# Multi_Room_Fire_Detection.net
KiCad netlist of a schematic drawn in EAGLE
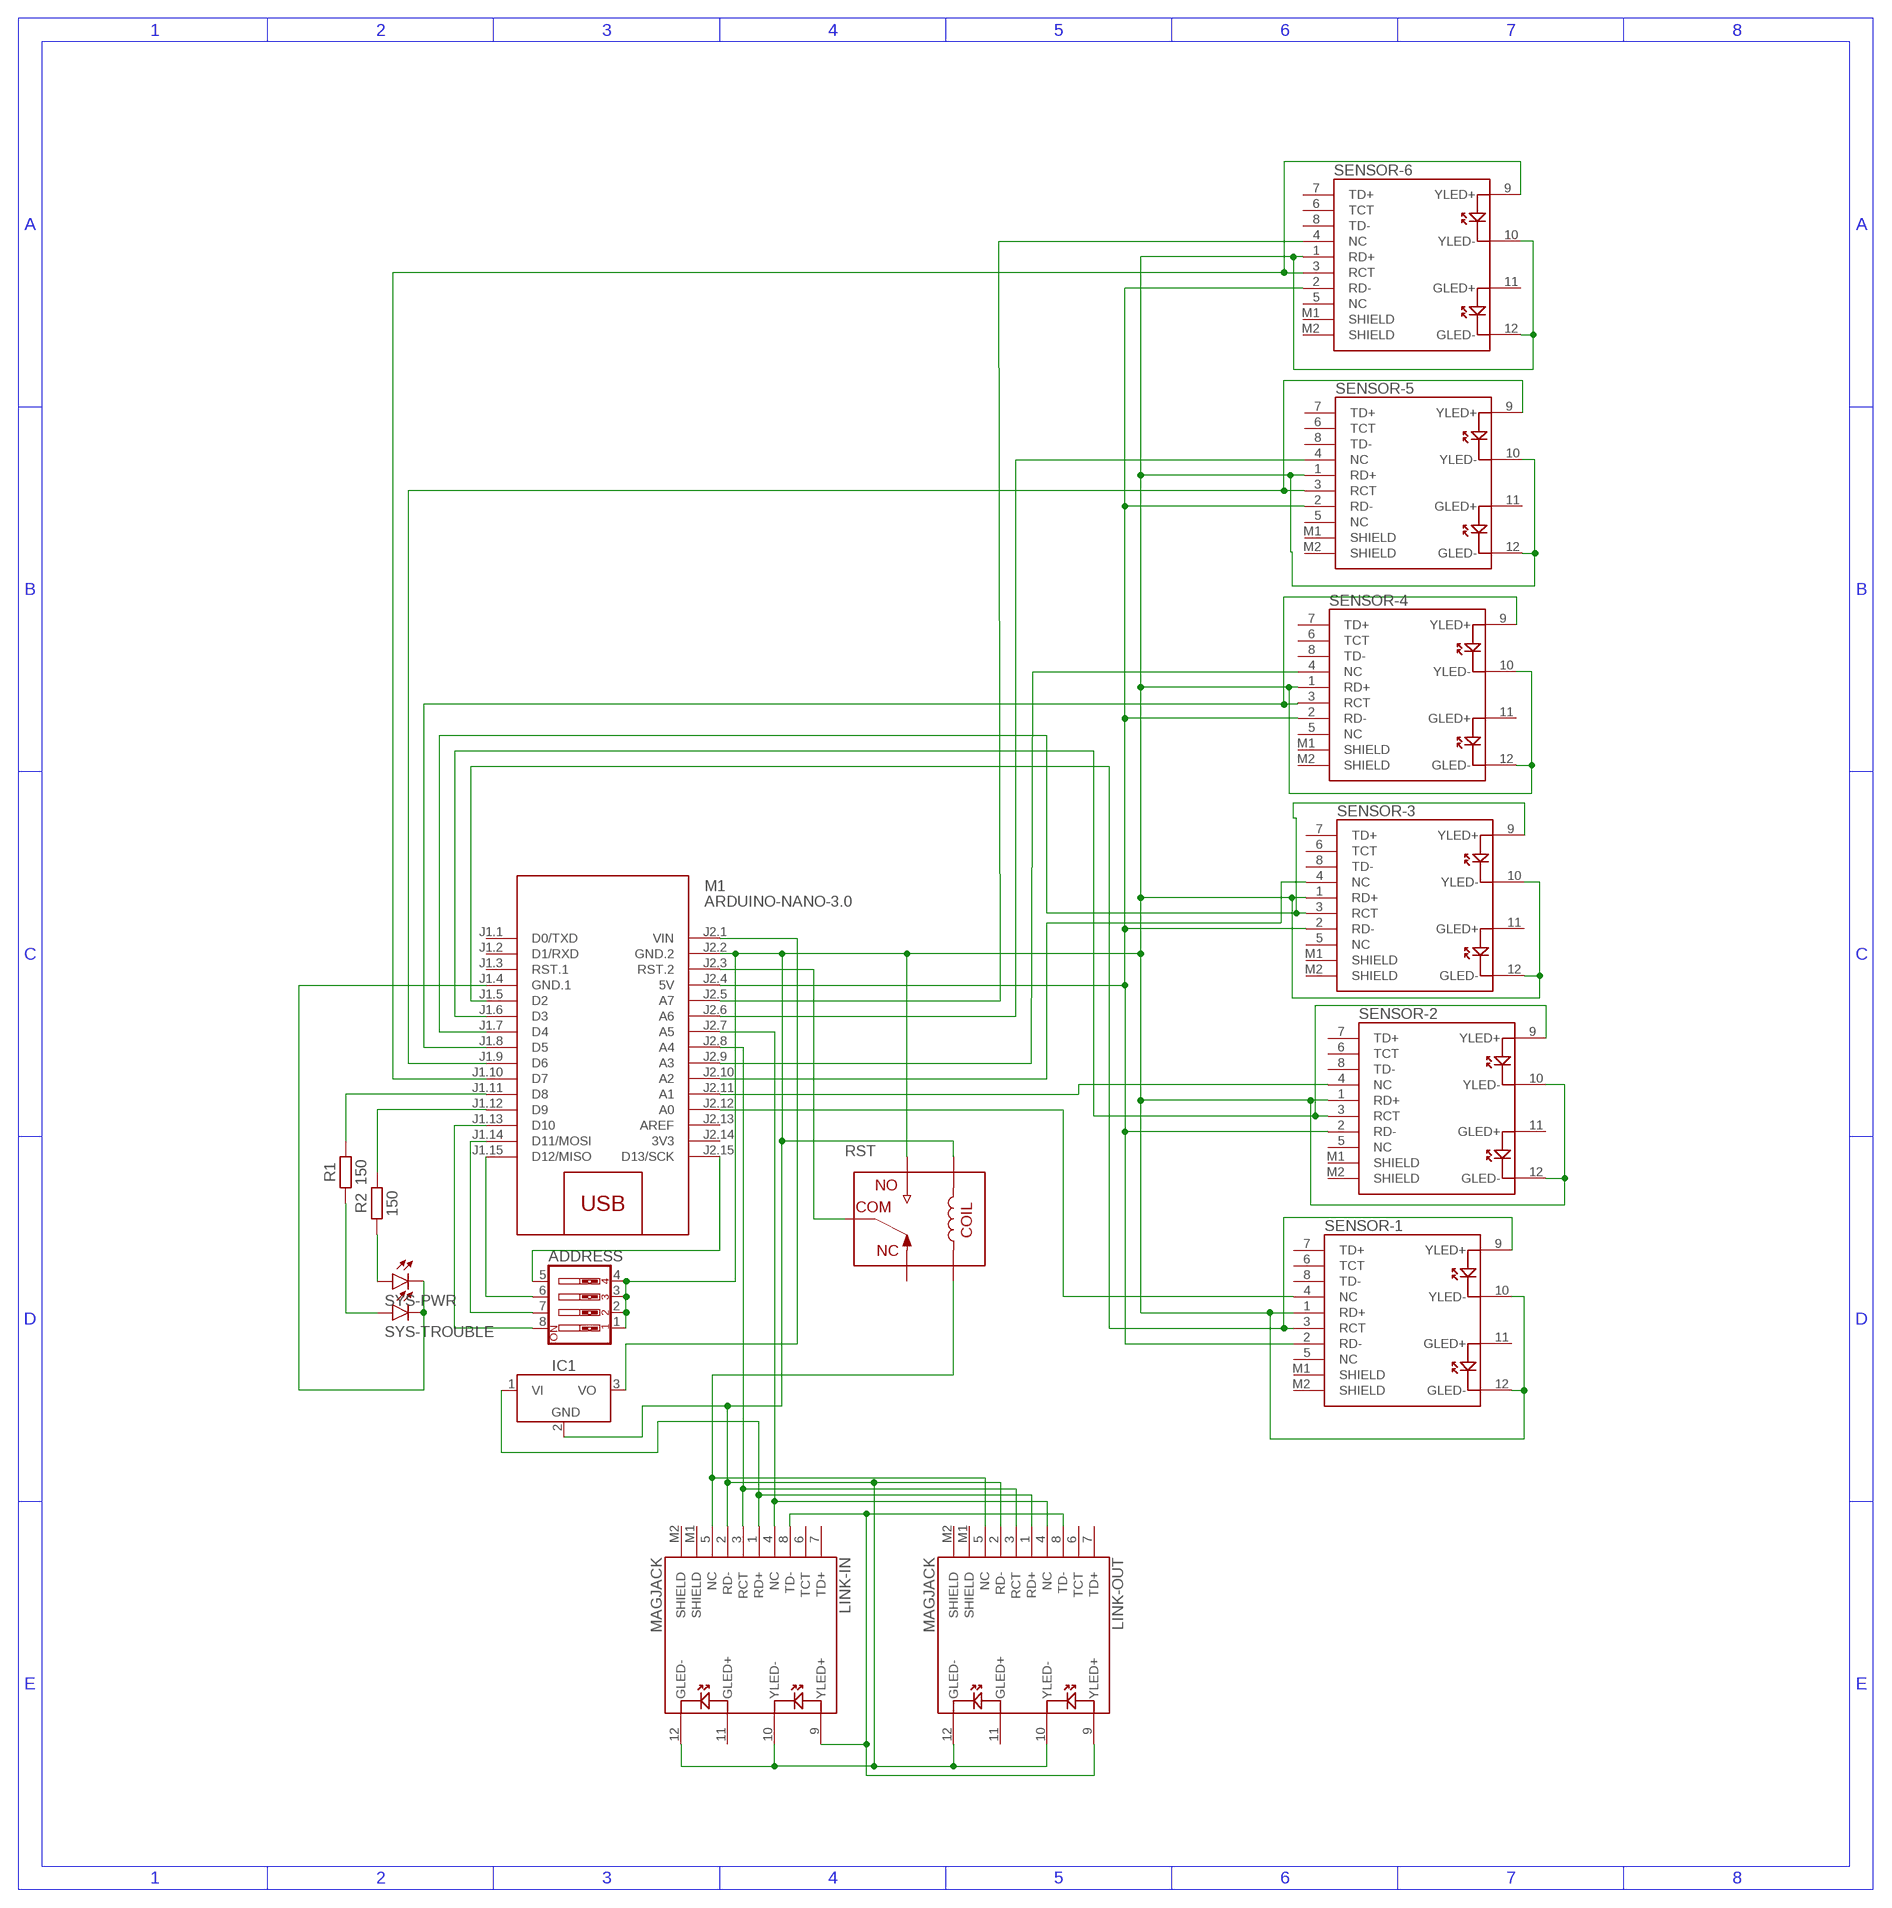
[diagram p0: schematic, sheet 1]

(export (version "E")
  (design (tool "Eeschema 10.0.6"))
  (components
    (comp (ref "ADDRESS")
      (value "SW_DIP-4")
      (footprint "eagle-import:EDG-04")
      (libsource (lib "eagle-import") (part "SW_DIP-4"))
    )
    (comp (ref "IC1")
      (value "LM7805_TO220V")
      (footprint "eagle-import:TO220V")
      (libsource (lib "eagle-import") (part "LM7805_TO220V"))
    )
    (comp (ref "LINK-IN")
      (value "MAGJACK")
      (footprint "eagle-import:MAGJACK")
      (libsource (lib "eagle-import") (part "MAGJACK"))
    )
    (comp (ref "LINK-OUT")
      (value "MAGJACK")
      (footprint "eagle-import:MAGJACK")
      (libsource (lib "eagle-import") (part "MAGJACK"))
    )
    (comp (ref "M1")
      (value "ARDUINO-NANO-3.0")
      (footprint "eagle-import:ARDUINO-NANO-3.0")
      (libsource (lib "eagle-import") (part "ARDUINO-NANO-3.0"))
    )
    (comp (ref "R1")
      (value "150")
      (footprint "eagle-import:RESAD724W46L381D178B")
      (libsource (lib "eagle-import") (part "RESISTOR_AXIAL-7.2MM-PITCH_"))
    )
    (comp (ref "R2")
      (value "150")
      (footprint "eagle-import:RESAD724W46L381D178B")
      (libsource (lib "eagle-import") (part "RESISTOR_AXIAL-7.2MM-PITCH_"))
    )
    (comp (ref "RST")
      (value "ACT112")
      (footprint "eagle-import:ACT112")
      (fields
        (field (name "DIGIKEY_PARTNO") "255-2591-ND")
        (field (name "MANUFACTURER") "Panasonic Electric Works")
        (field (name "CREATED_BY") "PCBLayout.com")
      )
      (libsource (lib "eagle-import") (part "ACT112"))
    )
    (comp (ref "SENSOR-1")
      (value "MAGJACK")
      (footprint "eagle-import:MAGJACK")
      (libsource (lib "eagle-import") (part "MAGJACK"))
    )
    (comp (ref "SENSOR-2")
      (value "MAGJACK")
      (footprint "eagle-import:MAGJACK")
      (libsource (lib "eagle-import") (part "MAGJACK"))
    )
    (comp (ref "SENSOR-3")
      (value "MAGJACK")
      (footprint "eagle-import:MAGJACK")
      (libsource (lib "eagle-import") (part "MAGJACK"))
    )
    (comp (ref "SENSOR-4")
      (value "MAGJACK")
      (footprint "eagle-import:MAGJACK")
      (libsource (lib "eagle-import") (part "MAGJACK"))
    )
    (comp (ref "SENSOR-5")
      (value "MAGJACK")
      (footprint "eagle-import:MAGJACK")
      (libsource (lib "eagle-import") (part "MAGJACK"))
    )
    (comp (ref "SENSOR-6")
      (value "MAGJACK")
      (footprint "eagle-import:MAGJACK")
      (libsource (lib "eagle-import") (part "MAGJACK"))
    )
    (comp (ref "SYS-PWR")
      (value "LED_GREEN")
      (footprint "eagle-import:LEDRD254W60D565H860B_G")
      (libsource (lib "eagle-import") (part "LED_RADIALGREEN_"))
    )
    (comp (ref "SYS-TROUBLE")
      (value "LED_RED")
      (footprint "eagle-import:LEDRD254W60D565H860B")
      (libsource (lib "eagle-import") (part "LED_RADIALRED_"))
    )
  )
  (nets
    (net (code "1") (name "/3V3") (class "Default")
      (node (ref "M1") (pin "J2.14") (pinfunction "3V3_J2.14") (pintype "power_in"))
    )
    (net (code "2") (name "Net-(IC1-GND)") (class "Default")
      (node (ref "ADDRESS") (pin "1") (pinfunction "1_1") (pintype "passive"))
      (node (ref "ADDRESS") (pin "2") (pinfunction "2_2") (pintype "passive"))
      (node (ref "ADDRESS") (pin "3") (pinfunction "3_3") (pintype "passive"))
      (node (ref "ADDRESS") (pin "4") (pinfunction "4_4") (pintype "passive"))
      (node (ref "IC1") (pin "2") (pinfunction "GND_2") (pintype "passive"))
      (node (ref "LINK-IN") (pin "10") (pinfunction "YLED-_10") (pintype "bidirectional"))
      (node (ref "LINK-IN") (pin "12") (pinfunction "GLED-_12") (pintype "bidirectional"))
      (node (ref "LINK-IN") (pin "2") (pinfunction "RD-_2") (pintype "bidirectional"))
      (node (ref "LINK-OUT") (pin "10") (pinfunction "YLED-_10") (pintype "bidirectional"))
      (node (ref "LINK-OUT") (pin "12") (pinfunction "GLED-_12") (pintype "bidirectional"))
      (node (ref "LINK-OUT") (pin "2") (pinfunction "RD-_2") (pintype "bidirectional"))
      (node (ref "M1") (pin "J2.2") (pinfunction "GND.2_J2.2") (pintype "power_in"))
      (node (ref "RST") (pin "1") (pinfunction "1_1") (pintype "passive"))
      (node (ref "RST") (pin "4") (pinfunction "4_4") (pintype "passive"))
      (node (ref "SENSOR-1") (pin "1") (pinfunction "RD+_1") (pintype "bidirectional"))
      (node (ref "SENSOR-1") (pin "10") (pinfunction "YLED-_10") (pintype "bidirectional"))
      (node (ref "SENSOR-1") (pin "12") (pinfunction "GLED-_12") (pintype "bidirectional"))
      (node (ref "SENSOR-2") (pin "1") (pinfunction "RD+_1") (pintype "bidirectional"))
      (node (ref "SENSOR-2") (pin "10") (pinfunction "YLED-_10") (pintype "bidirectional"))
      (node (ref "SENSOR-2") (pin "12") (pinfunction "GLED-_12") (pintype "bidirectional"))
      (node (ref "SENSOR-3") (pin "1") (pinfunction "RD+_1") (pintype "bidirectional"))
      (node (ref "SENSOR-3") (pin "10") (pinfunction "YLED-_10") (pintype "bidirectional"))
      (node (ref "SENSOR-3") (pin "12") (pinfunction "GLED-_12") (pintype "bidirectional"))
      (node (ref "SENSOR-4") (pin "1") (pinfunction "RD+_1") (pintype "bidirectional"))
      (node (ref "SENSOR-4") (pin "10") (pinfunction "YLED-_10") (pintype "bidirectional"))
      (node (ref "SENSOR-4") (pin "12") (pinfunction "GLED-_12") (pintype "bidirectional"))
      (node (ref "SENSOR-5") (pin "1") (pinfunction "RD+_1") (pintype "bidirectional"))
      (node (ref "SENSOR-5") (pin "10") (pinfunction "YLED-_10") (pintype "bidirectional"))
      (node (ref "SENSOR-5") (pin "12") (pinfunction "GLED-_12") (pintype "bidirectional"))
      (node (ref "SENSOR-6") (pin "1") (pinfunction "RD+_1") (pintype "bidirectional"))
      (node (ref "SENSOR-6") (pin "10") (pinfunction "YLED-_10") (pintype "bidirectional"))
      (node (ref "SENSOR-6") (pin "12") (pinfunction "GLED-_12") (pintype "bidirectional"))
    )
    (net (code "3") (name "Net-(IC1-VI)") (class "Default")
      (node (ref "IC1") (pin "1") (pinfunction "VI_1") (pintype "input"))
      (node (ref "LINK-IN") (pin "1") (pinfunction "RD+_1") (pintype "bidirectional"))
      (node (ref "LINK-OUT") (pin "1") (pinfunction "RD+_1") (pintype "bidirectional"))
    )
    (net (code "4") (name "Net-(IC1-VO)") (class "Default")
      (node (ref "IC1") (pin "3") (pinfunction "VO_3") (pintype "output"))
      (node (ref "M1") (pin "J2.1") (pinfunction "VIN_J2.1") (pintype "power_in"))
    )
    (net (code "5") (name "Net-(LINK-IN-NC-Pad5)") (class "Default")
      (node (ref "LINK-IN") (pin "5") (pinfunction "NC_5") (pintype "bidirectional"))
      (node (ref "LINK-OUT") (pin "5") (pinfunction "NC_5") (pintype "bidirectional"))
      (node (ref "RST") (pin "5") (pinfunction "5_5") (pintype "passive"))
    )
    (net (code "6") (name "Net-(LINK-IN-RCT)") (class "Default")
      (node (ref "LINK-IN") (pin "3") (pinfunction "RCT_3") (pintype "bidirectional"))
      (node (ref "LINK-OUT") (pin "3") (pinfunction "RCT_3") (pintype "bidirectional"))
      (node (ref "M1") (pin "J2.8") (pinfunction "A4_J2.8") (pintype "bidirectional"))
    )
    (net (code "7") (name "Net-(LINK-IN-TD-)") (class "Default")
      (node (ref "LINK-IN") (pin "8") (pinfunction "TD-_8") (pintype "bidirectional"))
      (node (ref "LINK-IN") (pin "9") (pinfunction "YLED+_9") (pintype "bidirectional"))
      (node (ref "LINK-OUT") (pin "8") (pinfunction "TD-_8") (pintype "bidirectional"))
      (node (ref "LINK-OUT") (pin "9") (pinfunction "YLED+_9") (pintype "bidirectional"))
    )
    (net (code "8") (name "Net-(M1-5V)") (class "Default")
      (node (ref "M1") (pin "J2.4") (pinfunction "5V_J2.4") (pintype "power_in"))
      (node (ref "SENSOR-1") (pin "2") (pinfunction "RD-_2") (pintype "bidirectional"))
      (node (ref "SENSOR-2") (pin "2") (pinfunction "RD-_2") (pintype "bidirectional"))
      (node (ref "SENSOR-3") (pin "2") (pinfunction "RD-_2") (pintype "bidirectional"))
      (node (ref "SENSOR-4") (pin "2") (pinfunction "RD-_2") (pintype "bidirectional"))
      (node (ref "SENSOR-5") (pin "2") (pinfunction "RD-_2") (pintype "bidirectional"))
      (node (ref "SENSOR-6") (pin "2") (pinfunction "RD-_2") (pintype "bidirectional"))
    )
    (net (code "9") (name "Net-(M1-A0)") (class "Default")
      (node (ref "M1") (pin "J2.12") (pinfunction "A0_J2.12") (pintype "bidirectional"))
      (node (ref "SENSOR-1") (pin "4") (pinfunction "NC_4") (pintype "bidirectional"))
    )
    (net (code "10") (name "Net-(M1-A1)") (class "Default")
      (node (ref "M1") (pin "J2.11") (pinfunction "A1_J2.11") (pintype "bidirectional"))
      (node (ref "SENSOR-2") (pin "4") (pinfunction "NC_4") (pintype "bidirectional"))
    )
    (net (code "11") (name "Net-(M1-A2)") (class "Default")
      (node (ref "M1") (pin "J2.10") (pinfunction "A2_J2.10") (pintype "bidirectional"))
      (node (ref "SENSOR-3") (pin "4") (pinfunction "NC_4") (pintype "bidirectional"))
    )
    (net (code "12") (name "Net-(M1-A3)") (class "Default")
      (node (ref "M1") (pin "J2.9") (pinfunction "A3_J2.9") (pintype "bidirectional"))
      (node (ref "SENSOR-4") (pin "4") (pinfunction "NC_4") (pintype "bidirectional"))
    )
    (net (code "13") (name "Net-(M1-A5)") (class "Default")
      (node (ref "LINK-IN") (pin "4") (pinfunction "NC_4") (pintype "bidirectional"))
      (node (ref "LINK-OUT") (pin "4") (pinfunction "NC_4") (pintype "bidirectional"))
      (node (ref "M1") (pin "J2.7") (pinfunction "A5_J2.7") (pintype "bidirectional"))
    )
    (net (code "14") (name "Net-(M1-A6)") (class "Default")
      (node (ref "M1") (pin "J2.6") (pinfunction "A6_J2.6") (pintype "bidirectional"))
      (node (ref "SENSOR-5") (pin "4") (pinfunction "NC_4") (pintype "bidirectional"))
    )
    (net (code "15") (name "Net-(M1-A7)") (class "Default")
      (node (ref "M1") (pin "J2.5") (pinfunction "A7_J2.5") (pintype "bidirectional"))
      (node (ref "SENSOR-6") (pin "4") (pinfunction "NC_4") (pintype "bidirectional"))
    )
    (net (code "16") (name "Net-(M1-D2)") (class "Default")
      (node (ref "M1") (pin "J1.5") (pinfunction "D2_J1.5") (pintype "bidirectional"))
      (node (ref "SENSOR-1") (pin "3") (pinfunction "RCT_3") (pintype "bidirectional"))
      (node (ref "SENSOR-1") (pin "9") (pinfunction "YLED+_9") (pintype "bidirectional"))
    )
    (net (code "17") (name "Net-(M1-D3)") (class "Default")
      (node (ref "M1") (pin "J1.6") (pinfunction "D3_J1.6") (pintype "bidirectional"))
      (node (ref "SENSOR-2") (pin "3") (pinfunction "RCT_3") (pintype "bidirectional"))
      (node (ref "SENSOR-2") (pin "9") (pinfunction "YLED+_9") (pintype "bidirectional"))
    )
    (net (code "18") (name "Net-(M1-D4)") (class "Default")
      (node (ref "M1") (pin "J1.7") (pinfunction "D4_J1.7") (pintype "bidirectional"))
      (node (ref "SENSOR-3") (pin "3") (pinfunction "RCT_3") (pintype "bidirectional"))
      (node (ref "SENSOR-3") (pin "9") (pinfunction "YLED+_9") (pintype "bidirectional"))
    )
    (net (code "19") (name "Net-(M1-D5)") (class "Default")
      (node (ref "M1") (pin "J1.8") (pinfunction "D5_J1.8") (pintype "bidirectional"))
      (node (ref "SENSOR-4") (pin "3") (pinfunction "RCT_3") (pintype "bidirectional"))
      (node (ref "SENSOR-4") (pin "9") (pinfunction "YLED+_9") (pintype "bidirectional"))
    )
    (net (code "20") (name "Net-(M1-D6)") (class "Default")
      (node (ref "M1") (pin "J1.9") (pinfunction "D6_J1.9") (pintype "bidirectional"))
      (node (ref "SENSOR-5") (pin "3") (pinfunction "RCT_3") (pintype "bidirectional"))
      (node (ref "SENSOR-5") (pin "9") (pinfunction "YLED+_9") (pintype "bidirectional"))
    )
    (net (code "21") (name "Net-(M1-D7)") (class "Default")
      (node (ref "M1") (pin "J1.10") (pinfunction "D7_J1.10") (pintype "bidirectional"))
      (node (ref "SENSOR-6") (pin "3") (pinfunction "RCT_3") (pintype "bidirectional"))
      (node (ref "SENSOR-6") (pin "9") (pinfunction "YLED+_9") (pintype "bidirectional"))
    )
    (net (code "22") (name "Net-(M1-D8)") (class "Default")
      (node (ref "M1") (pin "J1.11") (pinfunction "D8_J1.11") (pintype "bidirectional"))
      (node (ref "R1") (pin "2") (pinfunction "2_2") (pintype "passive"))
    )
    (net (code "23") (name "Net-(M1-D9)") (class "Default")
      (node (ref "M1") (pin "J1.12") (pinfunction "D9_J1.12") (pintype "bidirectional"))
      (node (ref "R2") (pin "2") (pinfunction "2_2") (pintype "passive"))
    )
    (net (code "24") (name "Net-(M1-D10)") (class "Default")
      (node (ref "ADDRESS") (pin "8") (pinfunction "8_8") (pintype "passive"))
      (node (ref "M1") (pin "J1.13") (pinfunction "D10_J1.13") (pintype "bidirectional"))
    )
    (net (code "25") (name "Net-(M1-D11{slash}MOSI)") (class "Default")
      (node (ref "ADDRESS") (pin "7") (pinfunction "7_7") (pintype "passive"))
      (node (ref "M1") (pin "J1.14") (pinfunction "D11/MOSI_J1.14") (pintype "bidirectional"))
    )
    (net (code "26") (name "Net-(M1-D12{slash}MISO)") (class "Default")
      (node (ref "ADDRESS") (pin "6") (pinfunction "6_6") (pintype "passive"))
      (node (ref "M1") (pin "J1.15") (pinfunction "D12/MISO_J1.15") (pintype "bidirectional"))
    )
    (net (code "27") (name "Net-(M1-D13{slash}SCK)") (class "Default")
      (node (ref "ADDRESS") (pin "5") (pinfunction "5_5") (pintype "passive"))
      (node (ref "M1") (pin "J2.15") (pinfunction "D13/SCK_J2.15") (pintype "bidirectional"))
    )
    (net (code "28") (name "Net-(M1-GND.1)") (class "Default")
      (node (ref "M1") (pin "J1.4") (pinfunction "GND.1_J1.4") (pintype "power_in"))
      (node (ref "SYS-PWR") (pin "2") (pinfunction "C_2") (pintype "passive"))
      (node (ref "SYS-TROUBLE") (pin "2") (pinfunction "C_2") (pintype "passive"))
    )
    (net (code "29") (name "Net-(M1-RST.2)") (class "Default")
      (node (ref "M1") (pin "J2.3") (pinfunction "RST.2_J2.3") (pintype "bidirectional"))
      (node (ref "RST") (pin "2") (pinfunction "2_2") (pintype "passive"))
    )
    (net (code "30") (name "Net-(SYS-PWR-A)") (class "Default")
      (node (ref "R2") (pin "1") (pinfunction "1_1") (pintype "passive"))
      (node (ref "SYS-PWR") (pin "1") (pinfunction "A_1") (pintype "passive"))
    )
    (net (code "31") (name "Net-(SYS-TROUBLE-A)") (class "Default")
      (node (ref "R1") (pin "1") (pinfunction "1_1") (pintype "passive"))
      (node (ref "SYS-TROUBLE") (pin "1") (pinfunction "A_1") (pintype "passive"))
    )
    (net (code "32") (name "unconnected-(LINK-IN-GLED+-Pad11)") (class "Default")
      (node (ref "LINK-IN") (pin "11") (pinfunction "GLED+_11") (pintype "bidirectional"))
    )
    (net (code "33") (name "unconnected-(LINK-IN-SHIELD-PadM1)") (class "Default")
      (node (ref "LINK-IN") (pin "M1") (pinfunction "SHIELD_M1") (pintype "bidirectional"))
    )
    (net (code "34") (name "unconnected-(LINK-IN-SHIELD-PadM2)") (class "Default")
      (node (ref "LINK-IN") (pin "M2") (pinfunction "SHIELD_M2") (pintype "bidirectional"))
    )
    (net (code "35") (name "unconnected-(LINK-IN-TCT-Pad6)") (class "Default")
      (node (ref "LINK-IN") (pin "6") (pinfunction "TCT_6") (pintype "bidirectional"))
    )
    (net (code "36") (name "unconnected-(LINK-IN-TD+-Pad7)") (class "Default")
      (node (ref "LINK-IN") (pin "7") (pinfunction "TD+_7") (pintype "bidirectional"))
    )
    (net (code "37") (name "unconnected-(LINK-OUT-GLED+-Pad11)") (class "Default")
      (node (ref "LINK-OUT") (pin "11") (pinfunction "GLED+_11") (pintype "bidirectional"))
    )
    (net (code "38") (name "unconnected-(LINK-OUT-SHIELD-PadM1)") (class "Default")
      (node (ref "LINK-OUT") (pin "M1") (pinfunction "SHIELD_M1") (pintype "bidirectional"))
    )
    (net (code "39") (name "unconnected-(LINK-OUT-SHIELD-PadM2)") (class "Default")
      (node (ref "LINK-OUT") (pin "M2") (pinfunction "SHIELD_M2") (pintype "bidirectional"))
    )
    (net (code "40") (name "unconnected-(LINK-OUT-TCT-Pad6)") (class "Default")
      (node (ref "LINK-OUT") (pin "6") (pinfunction "TCT_6") (pintype "bidirectional"))
    )
    (net (code "41") (name "unconnected-(LINK-OUT-TD+-Pad7)") (class "Default")
      (node (ref "LINK-OUT") (pin "7") (pinfunction "TD+_7") (pintype "bidirectional"))
    )
    (net (code "42") (name "unconnected-(M1-AREF-PadJ2.13)") (class "Default")
      (node (ref "M1") (pin "J2.13") (pinfunction "AREF_J2.13") (pintype "bidirectional"))
    )
    (net (code "43") (name "unconnected-(M1-D0{slash}TXD-PadJ1.1)") (class "Default")
      (node (ref "M1") (pin "J1.1") (pinfunction "D0/TXD_J1.1") (pintype "bidirectional"))
    )
    (net (code "44") (name "unconnected-(M1-D1{slash}RXD-PadJ1.2)") (class "Default")
      (node (ref "M1") (pin "J1.2") (pinfunction "D1/RXD_J1.2") (pintype "bidirectional"))
    )
    (net (code "45") (name "unconnected-(M1-RST.1-PadJ1.3)") (class "Default")
      (node (ref "M1") (pin "J1.3") (pinfunction "RST.1_J1.3") (pintype "bidirectional"))
    )
    (net (code "46") (name "unconnected-(RST-Pad3)") (class "Default")
      (node (ref "RST") (pin "3") (pinfunction "3_3") (pintype "passive"))
    )
    (net (code "47") (name "unconnected-(SENSOR-1-GLED+-Pad11)") (class "Default")
      (node (ref "SENSOR-1") (pin "11") (pinfunction "GLED+_11") (pintype "bidirectional"))
    )
    (net (code "48") (name "unconnected-(SENSOR-1-NC-Pad5)") (class "Default")
      (node (ref "SENSOR-1") (pin "5") (pinfunction "NC_5") (pintype "bidirectional"))
    )
    (net (code "49") (name "unconnected-(SENSOR-1-SHIELD-PadM1)") (class "Default")
      (node (ref "SENSOR-1") (pin "M1") (pinfunction "SHIELD_M1") (pintype "bidirectional"))
    )
    (net (code "50") (name "unconnected-(SENSOR-1-SHIELD-PadM2)") (class "Default")
      (node (ref "SENSOR-1") (pin "M2") (pinfunction "SHIELD_M2") (pintype "bidirectional"))
    )
    (net (code "51") (name "unconnected-(SENSOR-1-TCT-Pad6)") (class "Default")
      (node (ref "SENSOR-1") (pin "6") (pinfunction "TCT_6") (pintype "bidirectional"))
    )
    (net (code "52") (name "unconnected-(SENSOR-1-TD+-Pad7)") (class "Default")
      (node (ref "SENSOR-1") (pin "7") (pinfunction "TD+_7") (pintype "bidirectional"))
    )
    (net (code "53") (name "unconnected-(SENSOR-1-TD--Pad8)") (class "Default")
      (node (ref "SENSOR-1") (pin "8") (pinfunction "TD-_8") (pintype "bidirectional"))
    )
    (net (code "54") (name "unconnected-(SENSOR-2-GLED+-Pad11)") (class "Default")
      (node (ref "SENSOR-2") (pin "11") (pinfunction "GLED+_11") (pintype "bidirectional"))
    )
    (net (code "55") (name "unconnected-(SENSOR-2-NC-Pad5)") (class "Default")
      (node (ref "SENSOR-2") (pin "5") (pinfunction "NC_5") (pintype "bidirectional"))
    )
    (net (code "56") (name "unconnected-(SENSOR-2-SHIELD-PadM1)") (class "Default")
      (node (ref "SENSOR-2") (pin "M1") (pinfunction "SHIELD_M1") (pintype "bidirectional"))
    )
    (net (code "57") (name "unconnected-(SENSOR-2-SHIELD-PadM2)") (class "Default")
      (node (ref "SENSOR-2") (pin "M2") (pinfunction "SHIELD_M2") (pintype "bidirectional"))
    )
    (net (code "58") (name "unconnected-(SENSOR-2-TCT-Pad6)") (class "Default")
      (node (ref "SENSOR-2") (pin "6") (pinfunction "TCT_6") (pintype "bidirectional"))
    )
    (net (code "59") (name "unconnected-(SENSOR-2-TD+-Pad7)") (class "Default")
      (node (ref "SENSOR-2") (pin "7") (pinfunction "TD+_7") (pintype "bidirectional"))
    )
    (net (code "60") (name "unconnected-(SENSOR-2-TD--Pad8)") (class "Default")
      (node (ref "SENSOR-2") (pin "8") (pinfunction "TD-_8") (pintype "bidirectional"))
    )
    (net (code "61") (name "unconnected-(SENSOR-3-GLED+-Pad11)") (class "Default")
      (node (ref "SENSOR-3") (pin "11") (pinfunction "GLED+_11") (pintype "bidirectional"))
    )
    (net (code "62") (name "unconnected-(SENSOR-3-NC-Pad5)") (class "Default")
      (node (ref "SENSOR-3") (pin "5") (pinfunction "NC_5") (pintype "bidirectional"))
    )
    (net (code "63") (name "unconnected-(SENSOR-3-SHIELD-PadM1)") (class "Default")
      (node (ref "SENSOR-3") (pin "M1") (pinfunction "SHIELD_M1") (pintype "bidirectional"))
    )
    (net (code "64") (name "unconnected-(SENSOR-3-SHIELD-PadM2)") (class "Default")
      (node (ref "SENSOR-3") (pin "M2") (pinfunction "SHIELD_M2") (pintype "bidirectional"))
    )
    (net (code "65") (name "unconnected-(SENSOR-3-TCT-Pad6)") (class "Default")
      (node (ref "SENSOR-3") (pin "6") (pinfunction "TCT_6") (pintype "bidirectional"))
    )
    (net (code "66") (name "unconnected-(SENSOR-3-TD+-Pad7)") (class "Default")
      (node (ref "SENSOR-3") (pin "7") (pinfunction "TD+_7") (pintype "bidirectional"))
    )
    (net (code "67") (name "unconnected-(SENSOR-3-TD--Pad8)") (class "Default")
      (node (ref "SENSOR-3") (pin "8") (pinfunction "TD-_8") (pintype "bidirectional"))
    )
    (net (code "68") (name "unconnected-(SENSOR-4-GLED+-Pad11)") (class "Default")
      (node (ref "SENSOR-4") (pin "11") (pinfunction "GLED+_11") (pintype "bidirectional"))
    )
    (net (code "69") (name "unconnected-(SENSOR-4-NC-Pad5)") (class "Default")
      (node (ref "SENSOR-4") (pin "5") (pinfunction "NC_5") (pintype "bidirectional"))
    )
    (net (code "70") (name "unconnected-(SENSOR-4-SHIELD-PadM1)") (class "Default")
      (node (ref "SENSOR-4") (pin "M1") (pinfunction "SHIELD_M1") (pintype "bidirectional"))
    )
    (net (code "71") (name "unconnected-(SENSOR-4-SHIELD-PadM2)") (class "Default")
      (node (ref "SENSOR-4") (pin "M2") (pinfunction "SHIELD_M2") (pintype "bidirectional"))
    )
    (net (code "72") (name "unconnected-(SENSOR-4-TCT-Pad6)") (class "Default")
      (node (ref "SENSOR-4") (pin "6") (pinfunction "TCT_6") (pintype "bidirectional"))
    )
    (net (code "73") (name "unconnected-(SENSOR-4-TD+-Pad7)") (class "Default")
      (node (ref "SENSOR-4") (pin "7") (pinfunction "TD+_7") (pintype "bidirectional"))
    )
    (net (code "74") (name "unconnected-(SENSOR-4-TD--Pad8)") (class "Default")
      (node (ref "SENSOR-4") (pin "8") (pinfunction "TD-_8") (pintype "bidirectional"))
    )
    (net (code "75") (name "unconnected-(SENSOR-5-GLED+-Pad11)") (class "Default")
      (node (ref "SENSOR-5") (pin "11") (pinfunction "GLED+_11") (pintype "bidirectional"))
    )
    (net (code "76") (name "unconnected-(SENSOR-5-NC-Pad5)") (class "Default")
      (node (ref "SENSOR-5") (pin "5") (pinfunction "NC_5") (pintype "bidirectional"))
    )
    (net (code "77") (name "unconnected-(SENSOR-5-SHIELD-PadM1)") (class "Default")
      (node (ref "SENSOR-5") (pin "M1") (pinfunction "SHIELD_M1") (pintype "bidirectional"))
    )
    (net (code "78") (name "unconnected-(SENSOR-5-SHIELD-PadM2)") (class "Default")
      (node (ref "SENSOR-5") (pin "M2") (pinfunction "SHIELD_M2") (pintype "bidirectional"))
    )
    (net (code "79") (name "unconnected-(SENSOR-5-TCT-Pad6)") (class "Default")
      (node (ref "SENSOR-5") (pin "6") (pinfunction "TCT_6") (pintype "bidirectional"))
    )
    (net (code "80") (name "unconnected-(SENSOR-5-TD+-Pad7)") (class "Default")
      (node (ref "SENSOR-5") (pin "7") (pinfunction "TD+_7") (pintype "bidirectional"))
    )
    (net (code "81") (name "unconnected-(SENSOR-5-TD--Pad8)") (class "Default")
      (node (ref "SENSOR-5") (pin "8") (pinfunction "TD-_8") (pintype "bidirectional"))
    )
    (net (code "82") (name "unconnected-(SENSOR-6-GLED+-Pad11)") (class "Default")
      (node (ref "SENSOR-6") (pin "11") (pinfunction "GLED+_11") (pintype "bidirectional"))
    )
    (net (code "83") (name "unconnected-(SENSOR-6-NC-Pad5)") (class "Default")
      (node (ref "SENSOR-6") (pin "5") (pinfunction "NC_5") (pintype "bidirectional"))
    )
    (net (code "84") (name "unconnected-(SENSOR-6-SHIELD-PadM1)") (class "Default")
      (node (ref "SENSOR-6") (pin "M1") (pinfunction "SHIELD_M1") (pintype "bidirectional"))
    )
    (net (code "85") (name "unconnected-(SENSOR-6-SHIELD-PadM2)") (class "Default")
      (node (ref "SENSOR-6") (pin "M2") (pinfunction "SHIELD_M2") (pintype "bidirectional"))
    )
    (net (code "86") (name "unconnected-(SENSOR-6-TCT-Pad6)") (class "Default")
      (node (ref "SENSOR-6") (pin "6") (pinfunction "TCT_6") (pintype "bidirectional"))
    )
    (net (code "87") (name "unconnected-(SENSOR-6-TD+-Pad7)") (class "Default")
      (node (ref "SENSOR-6") (pin "7") (pinfunction "TD+_7") (pintype "bidirectional"))
    )
    (net (code "88") (name "unconnected-(SENSOR-6-TD--Pad8)") (class "Default")
      (node (ref "SENSOR-6") (pin "8") (pinfunction "TD-_8") (pintype "bidirectional"))
    )
  )
)
